# FRONT_BOARD.net
KiCad netlist of a schematic drawn in Altium Designer
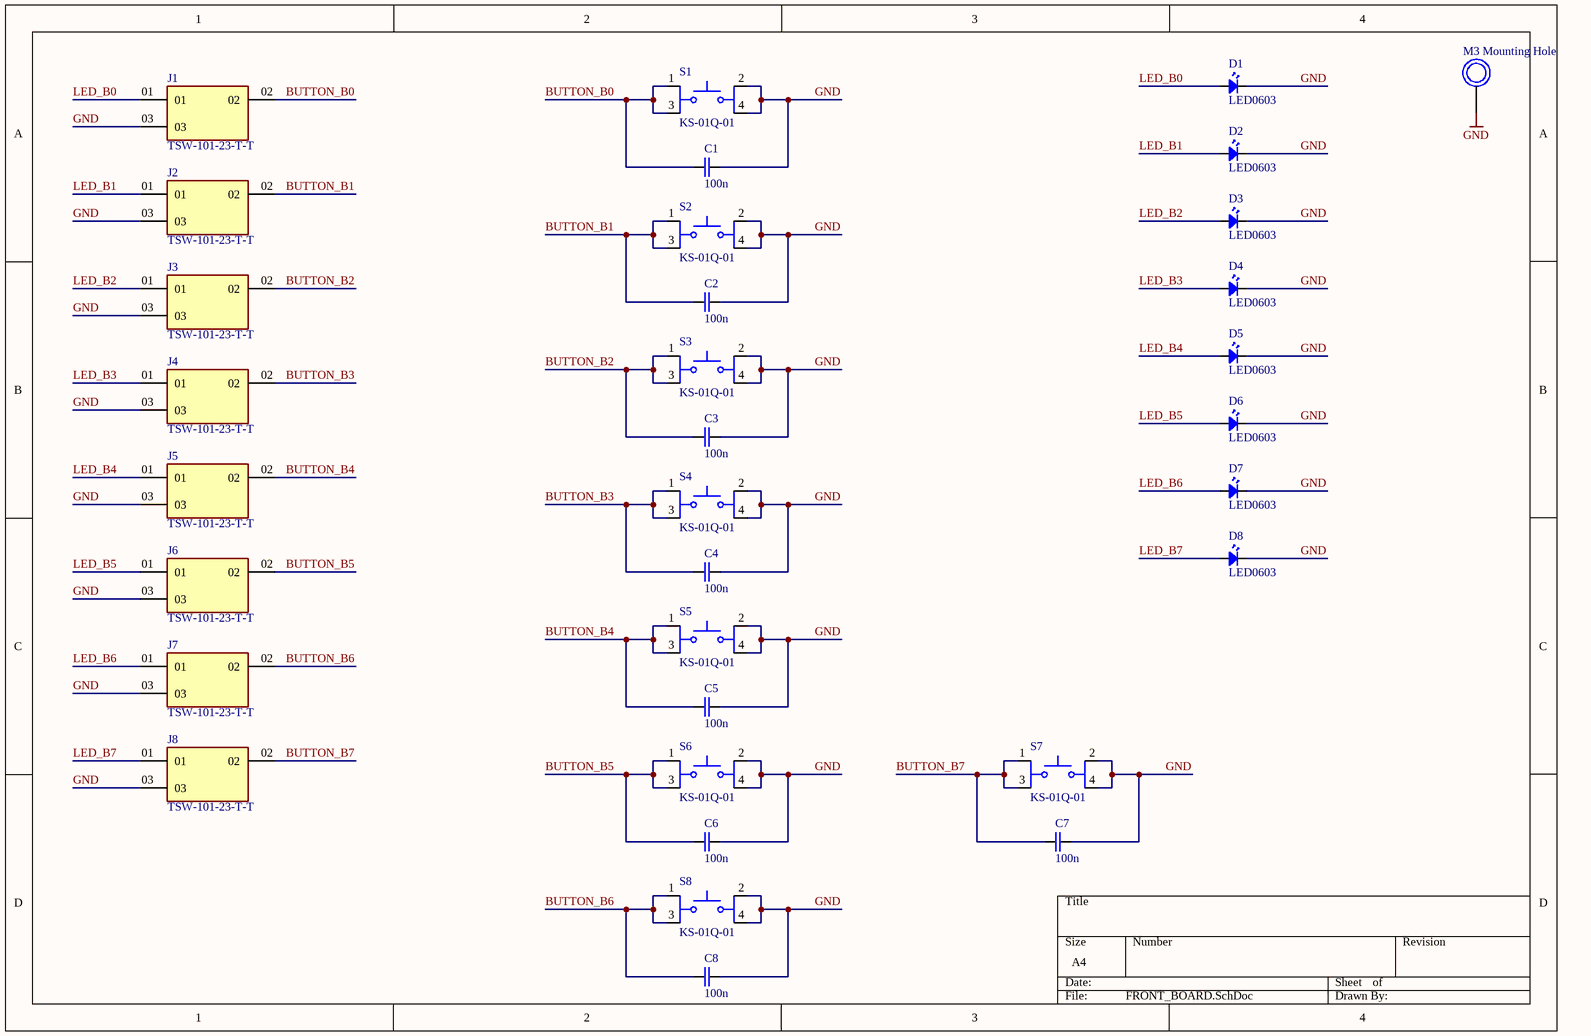
[diagram p0: FRONT_BOARD.SchDoc]

(export (version "E")
  (design (tool "Eeschema 10.0.6"))
  (components
    (comp (ref "C1")
      (value "100n")
      (footprint "C0603")
      (description "Generic 0603 SMD Ceramic Capacitor")
      (libsource (lib "PolSl Racing - Electrical") (part "Capacitor"))
    )
    (comp (ref "C2")
      (value "100n")
      (footprint "C0603")
      (description "Generic 0603 SMD Ceramic Capacitor")
      (libsource (lib "PolSl Racing - Electrical") (part "Capacitor"))
    )
    (comp (ref "C3")
      (value "100n")
      (footprint "C0603")
      (description "Generic 0603 SMD Ceramic Capacitor")
      (libsource (lib "PolSl Racing - Electrical") (part "Capacitor"))
    )
    (comp (ref "C4")
      (value "100n")
      (footprint "C0603")
      (description "Generic 0603 SMD Ceramic Capacitor")
      (libsource (lib "PolSl Racing - Electrical") (part "Capacitor"))
    )
    (comp (ref "C5")
      (value "100n")
      (footprint "C0603")
      (description "Generic 0603 SMD Ceramic Capacitor")
      (libsource (lib "PolSl Racing - Electrical") (part "Capacitor"))
    )
    (comp (ref "C6")
      (value "100n")
      (footprint "C0603")
      (description "Generic 0603 SMD Ceramic Capacitor")
      (libsource (lib "PolSl Racing - Electrical") (part "Capacitor"))
    )
    (comp (ref "C7")
      (value "100n")
      (footprint "C0603")
      (description "Generic 0603 SMD Ceramic Capacitor")
      (libsource (lib "PolSl Racing - Electrical") (part "Capacitor"))
    )
    (comp (ref "C8")
      (value "100n")
      (footprint "C0603")
      (description "Generic 0603 SMD Ceramic Capacitor")
      (libsource (lib "PolSl Racing - Electrical") (part "Capacitor"))
    )
    (comp (ref "D1")
      (value "LED0603")
      (footprint "LED0603")
      (description "0603 LED")
      (libsource (lib "PolSl Racing - Electrical") (part "LED"))
    )
    (comp (ref "D2")
      (value "LED0603")
      (footprint "LED0603")
      (description "0603 LED")
      (libsource (lib "PolSl Racing - Electrical") (part "LED"))
    )
    (comp (ref "D3")
      (value "LED0603")
      (footprint "LED0603")
      (description "0603 LED")
      (libsource (lib "PolSl Racing - Electrical") (part "LED"))
    )
    (comp (ref "D4")
      (value "LED0603")
      (footprint "LED0603")
      (description "0603 LED")
      (libsource (lib "PolSl Racing - Electrical") (part "LED"))
    )
    (comp (ref "D5")
      (value "LED0603")
      (footprint "LED0603")
      (description "0603 LED")
      (libsource (lib "PolSl Racing - Electrical") (part "LED"))
    )
    (comp (ref "D6")
      (value "LED0603")
      (footprint "LED0603")
      (description "0603 LED")
      (libsource (lib "PolSl Racing - Electrical") (part "LED"))
    )
    (comp (ref "D7")
      (value "LED0603")
      (footprint "LED0603")
      (description "0603 LED")
      (libsource (lib "PolSl Racing - Electrical") (part "LED"))
    )
    (comp (ref "D8")
      (value "LED0603")
      (footprint "LED0603")
      (description "0603 LED")
      (libsource (lib "PolSl Racing - Electrical") (part "LED"))
    )
    (comp (ref "J1")
      (value "TSW-101-23-T-T")
      (footprint "SAMTEC_TSW-101-23-T-T")
      (libsource (lib "TSW-101-23-T-T") (part "TSW-101-23-T-T"))
    )
    (comp (ref "J2")
      (value "TSW-101-23-T-T")
      (footprint "SAMTEC_TSW-101-23-T-T")
      (libsource (lib "TSW-101-23-T-T") (part "TSW-101-23-T-T"))
    )
    (comp (ref "J3")
      (value "TSW-101-23-T-T")
      (footprint "SAMTEC_TSW-101-23-T-T")
      (libsource (lib "TSW-101-23-T-T") (part "TSW-101-23-T-T"))
    )
    (comp (ref "J4")
      (value "TSW-101-23-T-T")
      (footprint "SAMTEC_TSW-101-23-T-T")
      (libsource (lib "TSW-101-23-T-T") (part "TSW-101-23-T-T"))
    )
    (comp (ref "J5")
      (value "TSW-101-23-T-T")
      (footprint "SAMTEC_TSW-101-23-T-T")
      (libsource (lib "TSW-101-23-T-T") (part "TSW-101-23-T-T"))
    )
    (comp (ref "J6")
      (value "TSW-101-23-T-T")
      (footprint "SAMTEC_TSW-101-23-T-T")
      (libsource (lib "TSW-101-23-T-T") (part "TSW-101-23-T-T"))
    )
    (comp (ref "J7")
      (value "TSW-101-23-T-T")
      (footprint "SAMTEC_TSW-101-23-T-T")
      (libsource (lib "TSW-101-23-T-T") (part "TSW-101-23-T-T"))
    )
    (comp (ref "J8")
      (value "TSW-101-23-T-T")
      (footprint "SAMTEC_TSW-101-23-T-T")
      (libsource (lib "TSW-101-23-T-T") (part "TSW-101-23-T-T"))
    )
    (comp (ref "MH1")
      (value "M3 Mounting Hole")
      (footprint "Copy of M4 Mounting Hole")
      (fields (field (name "MANUFACTURER") "Molex"))
      (libsource (lib "PolSl Racing - Electrical") (part "Mounting Hole"))
    )
    (comp (ref "S1")
      (value "KS-01Q-01")
      (footprint "SW_KS-01Q-01")
      (libsource (lib "KS-01Q-01") (part "KS-01Q-01"))
    )
    (comp (ref "S2")
      (value "KS-01Q-01")
      (footprint "SW_KS-01Q-01")
      (libsource (lib "KS-01Q-01") (part "KS-01Q-01"))
    )
    (comp (ref "S3")
      (value "KS-01Q-01")
      (footprint "SW_KS-01Q-01")
      (libsource (lib "KS-01Q-01") (part "KS-01Q-01"))
    )
    (comp (ref "S4")
      (value "KS-01Q-01")
      (footprint "SW_KS-01Q-01")
      (libsource (lib "KS-01Q-01") (part "KS-01Q-01"))
    )
    (comp (ref "S5")
      (value "KS-01Q-01")
      (footprint "SW_KS-01Q-01")
      (libsource (lib "KS-01Q-01") (part "KS-01Q-01"))
    )
    (comp (ref "S6")
      (value "KS-01Q-01")
      (footprint "SW_KS-01Q-01")
      (libsource (lib "KS-01Q-01") (part "KS-01Q-01"))
    )
    (comp (ref "S7")
      (value "KS-01Q-01")
      (footprint "SW_KS-01Q-01")
      (libsource (lib "KS-01Q-01") (part "KS-01Q-01"))
    )
    (comp (ref "S8")
      (value "KS-01Q-01")
      (footprint "SW_KS-01Q-01")
      (libsource (lib "KS-01Q-01") (part "KS-01Q-01"))
    )
  )
  (nets
    (net (code "1") (name "/BUTTON_B0") (class "Default")
      (node (ref "C1") (pin "1") (pinfunction "1_1") (pintype "passive"))
      (node (ref "J1") (pin "02") (pinfunction "02_02") (pintype "passive"))
      (node (ref "S1") (pin "1") (pinfunction "1_1") (pintype "passive"))
      (node (ref "S1") (pin "3") (pinfunction "3_3") (pintype "passive"))
    )
    (net (code "2") (name "/BUTTON_B1") (class "Default")
      (node (ref "C2") (pin "1") (pinfunction "1_1") (pintype "passive"))
      (node (ref "J2") (pin "02") (pinfunction "02_02") (pintype "passive"))
      (node (ref "S2") (pin "1") (pinfunction "1_1") (pintype "passive"))
      (node (ref "S2") (pin "3") (pinfunction "3_3") (pintype "passive"))
    )
    (net (code "3") (name "/BUTTON_B2") (class "Default")
      (node (ref "C3") (pin "1") (pinfunction "1_1") (pintype "passive"))
      (node (ref "J3") (pin "02") (pinfunction "02_02") (pintype "passive"))
      (node (ref "S3") (pin "1") (pinfunction "1_1") (pintype "passive"))
      (node (ref "S3") (pin "3") (pinfunction "3_3") (pintype "passive"))
    )
    (net (code "4") (name "/BUTTON_B3") (class "Default")
      (node (ref "C4") (pin "1") (pinfunction "1_1") (pintype "passive"))
      (node (ref "J4") (pin "02") (pinfunction "02_02") (pintype "passive"))
      (node (ref "S4") (pin "1") (pinfunction "1_1") (pintype "passive"))
      (node (ref "S4") (pin "3") (pinfunction "3_3") (pintype "passive"))
    )
    (net (code "5") (name "/BUTTON_B4") (class "Default")
      (node (ref "C5") (pin "1") (pinfunction "1_1") (pintype "passive"))
      (node (ref "J5") (pin "02") (pinfunction "02_02") (pintype "passive"))
      (node (ref "S5") (pin "1") (pinfunction "1_1") (pintype "passive"))
      (node (ref "S5") (pin "3") (pinfunction "3_3") (pintype "passive"))
    )
    (net (code "6") (name "/BUTTON_B5") (class "Default")
      (node (ref "C6") (pin "1") (pinfunction "1_1") (pintype "passive"))
      (node (ref "J6") (pin "02") (pinfunction "02_02") (pintype "passive"))
      (node (ref "S6") (pin "1") (pinfunction "1_1") (pintype "passive"))
      (node (ref "S6") (pin "3") (pinfunction "3_3") (pintype "passive"))
    )
    (net (code "7") (name "/BUTTON_B6") (class "Default")
      (node (ref "C8") (pin "1") (pinfunction "1_1") (pintype "passive"))
      (node (ref "J7") (pin "02") (pinfunction "02_02") (pintype "passive"))
      (node (ref "S8") (pin "1") (pinfunction "1_1") (pintype "passive"))
      (node (ref "S8") (pin "3") (pinfunction "3_3") (pintype "passive"))
    )
    (net (code "8") (name "/BUTTON_B7") (class "Default")
      (node (ref "C7") (pin "1") (pinfunction "1_1") (pintype "passive"))
      (node (ref "J8") (pin "02") (pinfunction "02_02") (pintype "passive"))
      (node (ref "S7") (pin "1") (pinfunction "1_1") (pintype "passive"))
      (node (ref "S7") (pin "3") (pinfunction "3_3") (pintype "passive"))
    )
    (net (code "9") (name "/LED_B0") (class "Default")
      (node (ref "D1") (pin "A") (pinfunction "A_A") (pintype "passive"))
      (node (ref "J1") (pin "01") (pinfunction "01_01") (pintype "passive"))
    )
    (net (code "10") (name "/LED_B1") (class "Default")
      (node (ref "D2") (pin "A") (pinfunction "A_A") (pintype "passive"))
      (node (ref "J2") (pin "01") (pinfunction "01_01") (pintype "passive"))
    )
    (net (code "11") (name "/LED_B2") (class "Default")
      (node (ref "D3") (pin "A") (pinfunction "A_A") (pintype "passive"))
      (node (ref "J3") (pin "01") (pinfunction "01_01") (pintype "passive"))
    )
    (net (code "12") (name "/LED_B3") (class "Default")
      (node (ref "D4") (pin "A") (pinfunction "A_A") (pintype "passive"))
      (node (ref "J4") (pin "01") (pinfunction "01_01") (pintype "passive"))
    )
    (net (code "13") (name "/LED_B4") (class "Default")
      (node (ref "D5") (pin "A") (pinfunction "A_A") (pintype "passive"))
      (node (ref "J5") (pin "01") (pinfunction "01_01") (pintype "passive"))
    )
    (net (code "14") (name "/LED_B5") (class "Default")
      (node (ref "D6") (pin "A") (pinfunction "A_A") (pintype "passive"))
      (node (ref "J6") (pin "01") (pinfunction "01_01") (pintype "passive"))
    )
    (net (code "15") (name "/LED_B6") (class "Default")
      (node (ref "D7") (pin "A") (pinfunction "A_A") (pintype "passive"))
      (node (ref "J7") (pin "01") (pinfunction "01_01") (pintype "passive"))
    )
    (net (code "16") (name "/LED_B7") (class "Default")
      (node (ref "D8") (pin "A") (pinfunction "A_A") (pintype "passive"))
      (node (ref "J8") (pin "01") (pinfunction "01_01") (pintype "passive"))
    )
    (net (code "17") (name "GND") (class "Default")
      (node (ref "C1") (pin "2") (pinfunction "2_2") (pintype "passive"))
      (node (ref "C2") (pin "2") (pinfunction "2_2") (pintype "passive"))
      (node (ref "C3") (pin "2") (pinfunction "2_2") (pintype "passive"))
      (node (ref "C4") (pin "2") (pinfunction "2_2") (pintype "passive"))
      (node (ref "C5") (pin "2") (pinfunction "2_2") (pintype "passive"))
      (node (ref "C6") (pin "2") (pinfunction "2_2") (pintype "passive"))
      (node (ref "C7") (pin "2") (pinfunction "2_2") (pintype "passive"))
      (node (ref "C8") (pin "2") (pinfunction "2_2") (pintype "passive"))
      (node (ref "D1") (pin "K") (pinfunction "K_K") (pintype "passive"))
      (node (ref "D2") (pin "K") (pinfunction "K_K") (pintype "passive"))
      (node (ref "D3") (pin "K") (pinfunction "K_K") (pintype "passive"))
      (node (ref "D4") (pin "K") (pinfunction "K_K") (pintype "passive"))
      (node (ref "D5") (pin "K") (pinfunction "K_K") (pintype "passive"))
      (node (ref "D6") (pin "K") (pinfunction "K_K") (pintype "passive"))
      (node (ref "D7") (pin "K") (pinfunction "K_K") (pintype "passive"))
      (node (ref "D8") (pin "K") (pinfunction "K_K") (pintype "passive"))
      (node (ref "J1") (pin "03") (pinfunction "03_03") (pintype "passive"))
      (node (ref "J2") (pin "03") (pinfunction "03_03") (pintype "passive"))
      (node (ref "J3") (pin "03") (pinfunction "03_03") (pintype "passive"))
      (node (ref "J4") (pin "03") (pinfunction "03_03") (pintype "passive"))
      (node (ref "J5") (pin "03") (pinfunction "03_03") (pintype "passive"))
      (node (ref "J6") (pin "03") (pinfunction "03_03") (pintype "passive"))
      (node (ref "J7") (pin "03") (pinfunction "03_03") (pintype "passive"))
      (node (ref "J8") (pin "03") (pinfunction "03_03") (pintype "passive"))
      (node (ref "MH1") (pin "1") (pinfunction "1_1") (pintype "passive"))
      (node (ref "S1") (pin "2") (pinfunction "2_2") (pintype "passive"))
      (node (ref "S1") (pin "4") (pinfunction "4_4") (pintype "passive"))
      (node (ref "S2") (pin "2") (pinfunction "2_2") (pintype "passive"))
      (node (ref "S2") (pin "4") (pinfunction "4_4") (pintype "passive"))
      (node (ref "S3") (pin "2") (pinfunction "2_2") (pintype "passive"))
      (node (ref "S3") (pin "4") (pinfunction "4_4") (pintype "passive"))
      (node (ref "S4") (pin "2") (pinfunction "2_2") (pintype "passive"))
      (node (ref "S4") (pin "4") (pinfunction "4_4") (pintype "passive"))
      (node (ref "S5") (pin "2") (pinfunction "2_2") (pintype "passive"))
      (node (ref "S5") (pin "4") (pinfunction "4_4") (pintype "passive"))
      (node (ref "S6") (pin "2") (pinfunction "2_2") (pintype "passive"))
      (node (ref "S6") (pin "4") (pinfunction "4_4") (pintype "passive"))
      (node (ref "S7") (pin "2") (pinfunction "2_2") (pintype "passive"))
      (node (ref "S7") (pin "4") (pinfunction "4_4") (pintype "passive"))
      (node (ref "S8") (pin "2") (pinfunction "2_2") (pintype "passive"))
      (node (ref "S8") (pin "4") (pinfunction "4_4") (pintype "passive"))
    )
  )
)
